# XDS100_V2.net
KiCad netlist of a schematic drawn in Altium Designer
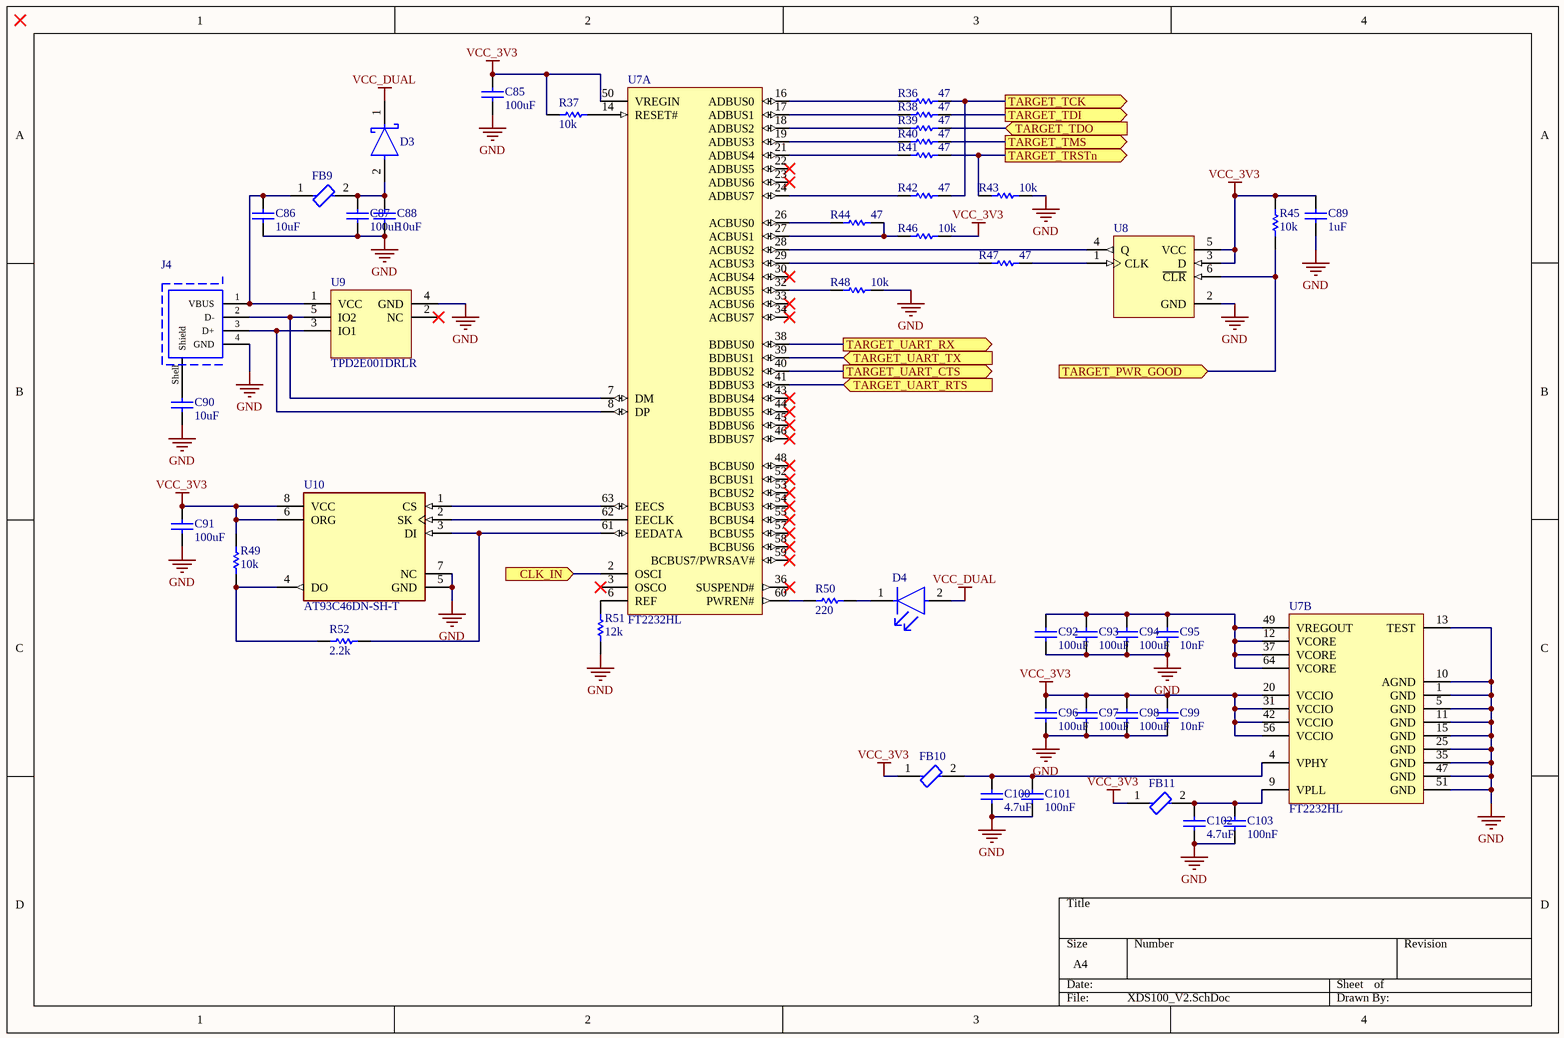
[diagram p0: XDS100_V2.SchDoc]

(export (version "E")
  (design (tool "Eeschema 10.0.6"))
  (components
    (comp (ref "C85")
      (value "100uF")
      (footprint "0805_C_S")
      (description "Capacitor")
      (fields (field (name "PUBLISHER") "Altium Limited"))
      (libsource (lib "Miscellaneous Devices") (part "Cap"))
    )
    (comp (ref "C86")
      (value "10uF")
      (footprint "0805_C_S")
      (description "Capacitor")
      (fields (field (name "PUBLISHER") "Altium Limited"))
      (libsource (lib "Miscellaneous Devices") (part "Cap"))
    )
    (comp (ref "C87")
      (value "100uF")
      (footprint "0805_C_S")
      (description "Capacitor")
      (fields (field (name "PUBLISHER") "Altium Limited"))
      (libsource (lib "Miscellaneous Devices") (part "Cap"))
    )
    (comp (ref "C88")
      (value "10uF")
      (footprint "0805_C_S")
      (description "Capacitor")
      (fields (field (name "PUBLISHER") "Altium Limited"))
      (libsource (lib "Miscellaneous Devices") (part "Cap"))
    )
    (comp (ref "C89")
      (value "1uF")
      (footprint "0805_C_S")
      (description "Capacitor")
      (fields (field (name "PUBLISHER") "Altium Limited"))
      (libsource (lib "Miscellaneous Devices") (part "Cap"))
    )
    (comp (ref "C90")
      (value "10uF")
      (footprint "0805_C_S")
      (description "Capacitor")
      (fields (field (name "PUBLISHER") "Altium Limited"))
      (libsource (lib "Miscellaneous Devices") (part "Cap"))
    )
    (comp (ref "C91")
      (value "100uF")
      (footprint "0805_C_S")
      (description "Capacitor")
      (fields (field (name "PUBLISHER") "Altium Limited"))
      (libsource (lib "Miscellaneous Devices") (part "Cap"))
    )
    (comp (ref "C92")
      (value "100uF")
      (footprint "0805_C_S")
      (description "Capacitor")
      (fields (field (name "PUBLISHER") "Altium Limited"))
      (libsource (lib "Miscellaneous Devices") (part "Cap"))
    )
    (comp (ref "C93")
      (value "100uF")
      (footprint "0805_C_S")
      (description "Capacitor")
      (fields (field (name "PUBLISHER") "Altium Limited"))
      (libsource (lib "Miscellaneous Devices") (part "Cap"))
    )
    (comp (ref "C94")
      (value "100uF")
      (footprint "0805_C_S")
      (description "Capacitor")
      (fields (field (name "PUBLISHER") "Altium Limited"))
      (libsource (lib "Miscellaneous Devices") (part "Cap"))
    )
    (comp (ref "C95")
      (value "10nF")
      (footprint "0805_C_S")
      (description "Capacitor")
      (fields (field (name "PUBLISHER") "Altium Limited"))
      (libsource (lib "Miscellaneous Devices") (part "Cap"))
    )
    (comp (ref "C96")
      (value "100uF")
      (footprint "0805_C_S")
      (description "Capacitor")
      (fields (field (name "PUBLISHER") "Altium Limited"))
      (libsource (lib "Miscellaneous Devices") (part "Cap"))
    )
    (comp (ref "C97")
      (value "100uF")
      (footprint "0805_C_S")
      (description "Capacitor")
      (fields (field (name "PUBLISHER") "Altium Limited"))
      (libsource (lib "Miscellaneous Devices") (part "Cap"))
    )
    (comp (ref "C98")
      (value "100uF")
      (footprint "0805_C_S")
      (description "Capacitor")
      (fields (field (name "PUBLISHER") "Altium Limited"))
      (libsource (lib "Miscellaneous Devices") (part "Cap"))
    )
    (comp (ref "C99")
      (value "10nF")
      (footprint "0805_C_S")
      (description "Capacitor")
      (fields (field (name "PUBLISHER") "Altium Limited"))
      (libsource (lib "Miscellaneous Devices") (part "Cap"))
    )
    (comp (ref "C100")
      (value "4.7uF")
      (footprint "0805_C_S")
      (description "Capacitor")
      (fields (field (name "PUBLISHER") "Altium Limited"))
      (libsource (lib "Miscellaneous Devices") (part "Cap"))
    )
    (comp (ref "C101")
      (value "100nF")
      (footprint "0805_C_S")
      (description "Capacitor")
      (fields (field (name "PUBLISHER") "Altium Limited"))
      (libsource (lib "Miscellaneous Devices") (part "Cap"))
    )
    (comp (ref "C102")
      (value "4.7uF")
      (footprint "0805_C_S")
      (description "Capacitor")
      (fields (field (name "PUBLISHER") "Altium Limited"))
      (libsource (lib "Miscellaneous Devices") (part "Cap"))
    )
    (comp (ref "C103")
      (value "100nF")
      (footprint "0805_C_S")
      (description "Capacitor")
      (fields (field (name "PUBLISHER") "Altium Limited"))
      (libsource (lib "Miscellaneous Devices") (part "Cap"))
    )
    (comp (ref "D3")
      (value "MBR0520LT1G")
      (footprint "FP-425-04-IPC_C")
      (description "DIODE SCHOTTKY 20V 500MA SOD123")
      (libsource (lib "Altium Content Vault") (part "1d6ec82d83fb6aee721767c19dac4b9"))
    )
    (comp (ref "D4")
      (value "LTST-C150AKT")
      (footprint "FP-LTST-C150AKT-MFG")
      (description "LED AMBER CLEAR SMD")
      (fields
        (field (name "MANUFACTURER") "Lite-On")
        (field (name "OCTOPART") "https://octopart.com/ltst-c150akt-lite-on-549804")
      )
      (libsource (lib "Altium Content Vault") (part "8706943c75ba83719d021d2fdc84c58"))
    )
    (comp (ref "FB9")
      (value "BLM21PG221SN1D")
      (footprint "FP-BLM21-0_2-t0_85-e0_5-IPC_B")
      (description "Chip Ferrite Bead, 0805, 220Ω @ 100MHz, 0.045Ω, 25%, 2A")
      (fields (field (name "TOLERANCE") "25%"))
      (libsource (lib "Altium Content Vault") (part "5f30dd21d616792df468990f7003faa"))
    )
    (comp (ref "FB10")
      (value "BLM21PG221SN1D")
      (footprint "FP-BLM21-0_2-t0_85-e0_5-IPC_B")
      (description "Chip Ferrite Bead, 0805, 220Ω @ 100MHz, 0.045Ω, 25%, 2A")
      (fields (field (name "TOLERANCE") "25%"))
      (libsource (lib "Altium Content Vault") (part "5f30dd21d616792df468990f7003faa"))
    )
    (comp (ref "FB11")
      (value "BLM21PG221SN1D")
      (footprint "FP-BLM21-0_2-t0_85-e0_5-IPC_B")
      (description "Chip Ferrite Bead, 0805, 220Ω @ 100MHz, 0.045Ω, 25%, 2A")
      (fields (field (name "TOLERANCE") "25%"))
      (libsource (lib "Altium Content Vault") (part "5f30dd21d616792df468990f7003faa"))
    )
    (comp (ref "J4")
      (value "62900416021")
      (footprint "62900416021")
      (description "USB 2.0 Type A Receptacle WR-COM, Horizontal, SMT")
      (fields (field (name "MANUFACTURER") "Wurth Elektronik") (field (name "PUBLISHER") "WurthElektronik"))
      (libsource (lib "Altium Content Vault") (part "WE-USB-4-1SHLD"))
    )
    (comp (ref "R36")
      (value "47")
      (footprint "0805_R_S")
      (description "Resistor")
      (fields (field (name "PUBLISHER") "Altium Limited"))
      (libsource (lib "Miscellaneous Devices") (part "Res1"))
    )
    (comp (ref "R37")
      (value "10k")
      (footprint "0805_R_S")
      (description "Resistor")
      (fields (field (name "PUBLISHER") "Altium Limited"))
      (libsource (lib "Miscellaneous Devices") (part "Res1"))
    )
    (comp (ref "R38")
      (value "47")
      (footprint "0805_R_S")
      (description "Resistor")
      (fields (field (name "PUBLISHER") "Altium Limited"))
      (libsource (lib "Miscellaneous Devices") (part "Res1"))
    )
    (comp (ref "R39")
      (value "47")
      (footprint "0805_R_S")
      (description "Resistor")
      (fields (field (name "PUBLISHER") "Altium Limited"))
      (libsource (lib "Miscellaneous Devices") (part "Res1"))
    )
    (comp (ref "R40")
      (value "47")
      (footprint "0805_R_S")
      (description "Resistor")
      (fields (field (name "PUBLISHER") "Altium Limited"))
      (libsource (lib "Miscellaneous Devices") (part "Res1"))
    )
    (comp (ref "R41")
      (value "47")
      (footprint "0805_R_S")
      (description "Resistor")
      (fields (field (name "PUBLISHER") "Altium Limited"))
      (libsource (lib "Miscellaneous Devices") (part "Res1"))
    )
    (comp (ref "R42")
      (value "47")
      (footprint "0805_R_S")
      (description "Resistor")
      (fields (field (name "PUBLISHER") "Altium Limited"))
      (libsource (lib "Miscellaneous Devices") (part "Res1"))
    )
    (comp (ref "R43")
      (value "10k")
      (footprint "0805_R_S")
      (description "Resistor")
      (fields (field (name "PUBLISHER") "Altium Limited"))
      (libsource (lib "Miscellaneous Devices") (part "Res1"))
    )
    (comp (ref "R44")
      (value "47")
      (footprint "0805_R_S")
      (description "Resistor")
      (fields (field (name "PUBLISHER") "Altium Limited"))
      (libsource (lib "Miscellaneous Devices") (part "Res1"))
    )
    (comp (ref "R45")
      (value "10k")
      (footprint "0805_R_S")
      (description "Resistor")
      (fields (field (name "PUBLISHER") "Altium Limited"))
      (libsource (lib "Miscellaneous Devices") (part "Res1"))
    )
    (comp (ref "R46")
      (value "10k")
      (footprint "0805_R_S")
      (description "Resistor")
      (fields (field (name "PUBLISHER") "Altium Limited"))
      (libsource (lib "Miscellaneous Devices") (part "Res1"))
    )
    (comp (ref "R47")
      (value "47")
      (footprint "0805_R_S")
      (description "Resistor")
      (fields (field (name "PUBLISHER") "Altium Limited"))
      (libsource (lib "Miscellaneous Devices") (part "Res1"))
    )
    (comp (ref "R48")
      (value "10k")
      (footprint "0805_R_S")
      (description "Resistor")
      (fields (field (name "PUBLISHER") "Altium Limited"))
      (libsource (lib "Miscellaneous Devices") (part "Res1"))
    )
    (comp (ref "R49")
      (value "10k")
      (footprint "0805_R_S")
      (description "Resistor")
      (fields (field (name "PUBLISHER") "Altium Limited"))
      (libsource (lib "Miscellaneous Devices") (part "Res1"))
    )
    (comp (ref "R50")
      (value "220")
      (footprint "0805_R_S")
      (description "Resistor")
      (fields (field (name "PUBLISHER") "Altium Limited"))
      (libsource (lib "Miscellaneous Devices") (part "Res1"))
    )
    (comp (ref "R51")
      (value "12k")
      (footprint "0805_R_S")
      (description "Resistor")
      (fields (field (name "PUBLISHER") "Altium Limited"))
      (libsource (lib "Miscellaneous Devices") (part "Res1"))
    )
    (comp (ref "R52")
      (value "2.2k")
      (footprint "0805_R_S")
      (description "Resistor")
      (fields (field (name "PUBLISHER") "Altium Limited"))
      (libsource (lib "Miscellaneous Devices") (part "Res1"))
    )
    (comp (ref "U7")
      (value "FT2232HL")
      (footprint "FTDI-LQFP-64_L")
      (fields (field (name "MANUFACTURER") "FTDI"))
      (libsource (lib "") (part "FTDI-FT2232HL-LQFP-64_1"))
    )
    (comp (ref "U8")
      (value "SN74LVC1G175DBVR")
      (footprint "DBV0006A_L")
      (description "Single D-Type Flip-Flop with Asynchronous Clear, DBV0006A, LARGE T&R")
      (fields
        (field (name "MANUFACTURER") "Texas Instruments")
        (field (name "GENERIC PART NUMBER") "SN74LVC1G175")
      )
      (libsource (lib "Altium Content Vault") (part "TI-SN74LVC1G175-6"))
    )
    (comp (ref "U9")
      (value "TPD2E001DRLR")
      (footprint "DRL0005A_L")
      (fields (field (name "MANUFACTURER") "Texas Instruments"))
      (libsource (lib "Altium Content Vault") (part "TI-TPD2E001-SOT_DRL-5"))
    )
    (comp (ref "U10")
      (value "AT93C46DN-SH-T")
      (footprint "FP-C04-057-SN-MFG")
      (description "IC EEPROM 1K SPI 2MHZ 8SOIC")
      (fields
        (field (name "MANUFACTURER") "Microchip")
        (field (name "OCTOPART") "https://octopart.com/at93c46dn-sh-t-microchip-77759177")
      )
      (libsource (lib "Altium Content Vault") (part "8bb9afc094b350e480db350c7247e52"))
    )
  )
  (nets
    (net (code "1") (name "/CLK_IN") (class "Default")
      (node (ref "U7") (pin "2") (pinfunction "OSCI_2") (pintype "passive"))
    )
    (net (code "2") (name "/TARGET_PWR_GOOD") (class "Default")
      (node (ref "R45") (pin "2") (pinfunction "2_2") (pintype "passive"))
      (node (ref "U8") (pin "6") (pinfunction "~{CLR}_6") (pintype "input"))
    )
    (net (code "3") (name "/TARGET_TCK") (class "Default")
      (node (ref "R36") (pin "2") (pinfunction "2_2") (pintype "passive"))
      (node (ref "R42") (pin "2") (pinfunction "2_2") (pintype "passive"))
    )
    (net (code "4") (name "/TARGET_TDI") (class "Default")
      (node (ref "R38") (pin "2") (pinfunction "2_2") (pintype "passive"))
    )
    (net (code "5") (name "/TARGET_TDO") (class "Default")
      (node (ref "R39") (pin "2") (pinfunction "2_2") (pintype "passive"))
    )
    (net (code "6") (name "/TARGET_TMS") (class "Default")
      (node (ref "R40") (pin "2") (pinfunction "2_2") (pintype "passive"))
    )
    (net (code "7") (name "/TARGET_TRSTn") (class "Default")
      (node (ref "R41") (pin "2") (pinfunction "2_2") (pintype "passive"))
      (node (ref "R43") (pin "1") (pinfunction "1_1") (pintype "passive"))
    )
    (net (code "8") (name "/TARGET_UART_CTS") (class "Default")
      (node (ref "U7") (pin "40") (pinfunction "BDBUS2_40") (pintype "bidirectional"))
    )
    (net (code "9") (name "/TARGET_UART_RTS") (class "Default")
      (node (ref "U7") (pin "41") (pinfunction "BDBUS3_41") (pintype "bidirectional"))
    )
    (net (code "10") (name "/TARGET_UART_RX") (class "Default")
      (node (ref "U7") (pin "38") (pinfunction "BDBUS0_38") (pintype "bidirectional"))
    )
    (net (code "11") (name "/TARGET_UART_TX") (class "Default")
      (node (ref "U7") (pin "39") (pinfunction "BDBUS1_39") (pintype "bidirectional"))
    )
    (net (code "12") (name "GND") (class "Default")
      (node (ref "C100") (pin "1") (pinfunction "1_1") (pintype "passive"))
      (node (ref "C101") (pin "1") (pinfunction "1_1") (pintype "passive"))
      (node (ref "C102") (pin "1") (pinfunction "1_1") (pintype "passive"))
      (node (ref "C103") (pin "1") (pinfunction "1_1") (pintype "passive"))
      (node (ref "C85") (pin "1") (pinfunction "1_1") (pintype "passive"))
      (node (ref "C86") (pin "1") (pinfunction "1_1") (pintype "passive"))
      (node (ref "C87") (pin "1") (pinfunction "1_1") (pintype "passive"))
      (node (ref "C88") (pin "1") (pinfunction "1_1") (pintype "passive"))
      (node (ref "C89") (pin "1") (pinfunction "1_1") (pintype "passive"))
      (node (ref "C90") (pin "1") (pinfunction "1_1") (pintype "passive"))
      (node (ref "C91") (pin "1") (pinfunction "1_1") (pintype "passive"))
      (node (ref "C92") (pin "1") (pinfunction "1_1") (pintype "passive"))
      (node (ref "C93") (pin "1") (pinfunction "1_1") (pintype "passive"))
      (node (ref "C94") (pin "1") (pinfunction "1_1") (pintype "passive"))
      (node (ref "C95") (pin "1") (pinfunction "1_1") (pintype "passive"))
      (node (ref "C96") (pin "1") (pinfunction "1_1") (pintype "passive"))
      (node (ref "C97") (pin "1") (pinfunction "1_1") (pintype "passive"))
      (node (ref "C98") (pin "1") (pinfunction "1_1") (pintype "passive"))
      (node (ref "C99") (pin "1") (pinfunction "1_1") (pintype "passive"))
      (node (ref "J4") (pin "4") (pinfunction "GND_4") (pintype "passive"))
      (node (ref "R43") (pin "2") (pinfunction "2_2") (pintype "passive"))
      (node (ref "R48") (pin "2") (pinfunction "2_2") (pintype "passive"))
      (node (ref "R51") (pin "2") (pinfunction "2_2") (pintype "passive"))
      (node (ref "U10") (pin "5") (pinfunction "GND_5") (pintype "power_in"))
      (node (ref "U10") (pin "7") (pinfunction "NC_7") (pintype "passive"))
      (node (ref "U7") (pin "1") (pinfunction "GND_1") (pintype "power_in"))
      (node (ref "U7") (pin "10") (pinfunction "AGND_10") (pintype "power_in"))
      (node (ref "U7") (pin "11") (pinfunction "GND_11") (pintype "power_in"))
      (node (ref "U7") (pin "13") (pinfunction "TEST_13") (pintype "passive"))
      (node (ref "U7") (pin "15") (pinfunction "GND_15") (pintype "power_in"))
      (node (ref "U7") (pin "25") (pinfunction "GND_25") (pintype "power_in"))
      (node (ref "U7") (pin "35") (pinfunction "GND_35") (pintype "power_in"))
      (node (ref "U7") (pin "47") (pinfunction "GND_47") (pintype "power_in"))
      (node (ref "U7") (pin "5") (pinfunction "GND_5") (pintype "power_in"))
      (node (ref "U7") (pin "51") (pinfunction "GND_51") (pintype "power_in"))
      (node (ref "U8") (pin "2") (pinfunction "GND_2") (pintype "power_in"))
      (node (ref "U9") (pin "4") (pinfunction "GND_4") (pintype "power_in"))
    )
    (net (code "13") (name "Net-(D3-A)") (class "Default")
      (node (ref "C87") (pin "2") (pinfunction "2_2") (pintype "passive"))
      (node (ref "C88") (pin "2") (pinfunction "2_2") (pintype "passive"))
      (node (ref "D3") (pin "2") (pinfunction "A_2") (pintype "passive"))
      (node (ref "FB9") (pin "2") (pinfunction "2_2") (pintype "passive"))
    )
    (net (code "14") (name "Net-(D4-C)") (class "Default")
      (node (ref "D4") (pin "1") (pinfunction "C_1") (pintype "passive"))
      (node (ref "R50") (pin "2") (pinfunction "2_2") (pintype "passive"))
    )
    (net (code "15") (name "Net-(J4-D+)") (class "Default")
      (node (ref "J4") (pin "3") (pinfunction "D+_3") (pintype "passive"))
      (node (ref "U7") (pin "8") (pinfunction "DP_8") (pintype "bidirectional"))
      (node (ref "U9") (pin "3") (pinfunction "IO1_3") (pintype "passive"))
    )
    (net (code "16") (name "Net-(J4-D-)") (class "Default")
      (node (ref "J4") (pin "2") (pinfunction "D-_2") (pintype "passive"))
      (node (ref "U7") (pin "7") (pinfunction "DM_7") (pintype "bidirectional"))
      (node (ref "U9") (pin "5") (pinfunction "IO2_5") (pintype "passive"))
    )
    (net (code "17") (name "Net-(J4-Shield)") (class "Default")
      (node (ref "C90") (pin "2") (pinfunction "2_2") (pintype "passive"))
      (node (ref "J4") (pin "Shell") (pinfunction "Shield_Shell") (pintype "passive"))
    )
    (net (code "18") (name "Net-(J4-VBUS)") (class "Default")
      (node (ref "C86") (pin "2") (pinfunction "2_2") (pintype "passive"))
      (node (ref "FB9") (pin "1") (pinfunction "1_1") (pintype "passive"))
      (node (ref "J4") (pin "1") (pinfunction "VBUS_1") (pintype "passive"))
      (node (ref "U9") (pin "1") (pinfunction "VCC_1") (pintype "power_in"))
    )
    (net (code "19") (name "Net-(U7A-ACBUS0)") (class "Default")
      (node (ref "R44") (pin "1") (pinfunction "1_1") (pintype "passive"))
      (node (ref "U7") (pin "26") (pinfunction "ACBUS0_26") (pintype "bidirectional"))
    )
    (net (code "20") (name "Net-(U7A-ACBUS1)") (class "Default")
      (node (ref "R44") (pin "2") (pinfunction "2_2") (pintype "passive"))
      (node (ref "R46") (pin "1") (pinfunction "1_1") (pintype "passive"))
      (node (ref "U7") (pin "27") (pinfunction "ACBUS1_27") (pintype "bidirectional"))
    )
    (net (code "21") (name "Net-(U7A-ACBUS2)") (class "Default")
      (node (ref "U7") (pin "28") (pinfunction "ACBUS2_28") (pintype "bidirectional"))
      (node (ref "U8") (pin "4") (pinfunction "Q_4") (pintype "output"))
    )
    (net (code "22") (name "Net-(U7A-ACBUS3)") (class "Default")
      (node (ref "R47") (pin "1") (pinfunction "1_1") (pintype "passive"))
      (node (ref "U7") (pin "29") (pinfunction "ACBUS3_29") (pintype "bidirectional"))
    )
    (net (code "23") (name "Net-(U7A-ACBUS5)") (class "Default")
      (node (ref "R48") (pin "1") (pinfunction "1_1") (pintype "passive"))
      (node (ref "U7") (pin "32") (pinfunction "ACBUS5_32") (pintype "bidirectional"))
    )
    (net (code "24") (name "Net-(U7A-ADBUS0)") (class "Default")
      (node (ref "R36") (pin "1") (pinfunction "1_1") (pintype "passive"))
      (node (ref "U7") (pin "16") (pinfunction "ADBUS0_16") (pintype "bidirectional"))
    )
    (net (code "25") (name "Net-(U7A-ADBUS1)") (class "Default")
      (node (ref "R38") (pin "1") (pinfunction "1_1") (pintype "passive"))
      (node (ref "U7") (pin "17") (pinfunction "ADBUS1_17") (pintype "bidirectional"))
    )
    (net (code "26") (name "Net-(U7A-ADBUS2)") (class "Default")
      (node (ref "R39") (pin "1") (pinfunction "1_1") (pintype "passive"))
      (node (ref "U7") (pin "18") (pinfunction "ADBUS2_18") (pintype "bidirectional"))
    )
    (net (code "27") (name "Net-(U7A-ADBUS3)") (class "Default")
      (node (ref "R40") (pin "1") (pinfunction "1_1") (pintype "passive"))
      (node (ref "U7") (pin "19") (pinfunction "ADBUS3_19") (pintype "bidirectional"))
    )
    (net (code "28") (name "Net-(U7A-ADBUS4)") (class "Default")
      (node (ref "R41") (pin "1") (pinfunction "1_1") (pintype "passive"))
      (node (ref "U7") (pin "21") (pinfunction "ADBUS4_21") (pintype "bidirectional"))
    )
    (net (code "29") (name "Net-(U7A-ADBUS7)") (class "Default")
      (node (ref "R42") (pin "1") (pinfunction "1_1") (pintype "passive"))
      (node (ref "U7") (pin "24") (pinfunction "ADBUS7_24") (pintype "bidirectional"))
    )
    (net (code "30") (name "Net-(U7A-PWREN#)") (class "Default")
      (node (ref "R50") (pin "1") (pinfunction "1_1") (pintype "passive"))
      (node (ref "U7") (pin "60") (pinfunction "PWREN#_60") (pintype "output"))
    )
    (net (code "31") (name "Net-(U7A-REF)") (class "Default")
      (node (ref "R51") (pin "1") (pinfunction "1_1") (pintype "passive"))
      (node (ref "U7") (pin "6") (pinfunction "REF_6") (pintype "passive"))
    )
    (net (code "32") (name "Net-(U7A-RESET#)") (class "Default")
      (node (ref "R37") (pin "2") (pinfunction "2_2") (pintype "passive"))
      (node (ref "U7") (pin "14") (pinfunction "RESET#_14") (pintype "input"))
    )
    (net (code "33") (name "Net-(U7B-VPHY)") (class "Default")
      (node (ref "C100") (pin "2") (pinfunction "2_2") (pintype "passive"))
      (node (ref "C101") (pin "2") (pinfunction "2_2") (pintype "passive"))
      (node (ref "FB10") (pin "2") (pinfunction "2_2") (pintype "passive"))
      (node (ref "U7") (pin "4") (pinfunction "VPHY_4") (pintype "power_in"))
    )
    (net (code "34") (name "Net-(U7B-VPLL)") (class "Default")
      (node (ref "C102") (pin "2") (pinfunction "2_2") (pintype "passive"))
      (node (ref "C103") (pin "2") (pinfunction "2_2") (pintype "passive"))
      (node (ref "FB11") (pin "2") (pinfunction "2_2") (pintype "passive"))
      (node (ref "U7") (pin "9") (pinfunction "VPLL_9") (pintype "power_in"))
    )
    (net (code "35") (name "Net-(U7B-VREGOUT)") (class "Default")
      (node (ref "C92") (pin "2") (pinfunction "2_2") (pintype "passive"))
      (node (ref "C93") (pin "2") (pinfunction "2_2") (pintype "passive"))
      (node (ref "C94") (pin "2") (pinfunction "2_2") (pintype "passive"))
      (node (ref "C95") (pin "2") (pinfunction "2_2") (pintype "passive"))
      (node (ref "U7") (pin "12") (pinfunction "VCORE_12") (pintype "power_in"))
      (node (ref "U7") (pin "37") (pinfunction "VCORE_37") (pintype "power_in"))
      (node (ref "U7") (pin "49") (pinfunction "VREGOUT_49") (pintype "power_in"))
      (node (ref "U7") (pin "64") (pinfunction "VCORE_64") (pintype "power_in"))
    )
    (net (code "36") (name "Net-(U8-CLK)") (class "Default")
      (node (ref "R47") (pin "2") (pinfunction "2_2") (pintype "passive"))
      (node (ref "U8") (pin "1") (pinfunction "CLK_1") (pintype "input"))
    )
    (net (code "37") (name "Net-(U10-CS)") (class "Default")
      (node (ref "U10") (pin "1") (pinfunction "CS_1") (pintype "input"))
      (node (ref "U7") (pin "63") (pinfunction "EECS_63") (pintype "bidirectional"))
    )
    (net (code "38") (name "Net-(U10-DI)") (class "Default")
      (node (ref "R52") (pin "2") (pinfunction "2_2") (pintype "passive"))
      (node (ref "U10") (pin "3") (pinfunction "DI_3") (pintype "input"))
      (node (ref "U7") (pin "61") (pinfunction "EEDATA_61") (pintype "bidirectional"))
    )
    (net (code "39") (name "Net-(U10-DO)") (class "Default")
      (node (ref "R49") (pin "2") (pinfunction "2_2") (pintype "passive"))
      (node (ref "R52") (pin "1") (pinfunction "1_1") (pintype "passive"))
      (node (ref "U10") (pin "4") (pinfunction "DO_4") (pintype "output"))
    )
    (net (code "40") (name "Net-(U10-SK)") (class "Default")
      (node (ref "U10") (pin "2") (pinfunction "SK_2") (pintype "input"))
      (node (ref "U7") (pin "62") (pinfunction "EECLK_62") (pintype "tri_state"))
    )
    (net (code "41") (name "VCC_3V3") (class "Default")
      (node (ref "C85") (pin "2") (pinfunction "2_2") (pintype "passive"))
      (node (ref "C89") (pin "2") (pinfunction "2_2") (pintype "passive"))
      (node (ref "C91") (pin "2") (pinfunction "2_2") (pintype "passive"))
      (node (ref "C96") (pin "2") (pinfunction "2_2") (pintype "passive"))
      (node (ref "C97") (pin "2") (pinfunction "2_2") (pintype "passive"))
      (node (ref "C98") (pin "2") (pinfunction "2_2") (pintype "passive"))
      (node (ref "C99") (pin "2") (pinfunction "2_2") (pintype "passive"))
      (node (ref "FB10") (pin "1") (pinfunction "1_1") (pintype "passive"))
      (node (ref "FB11") (pin "1") (pinfunction "1_1") (pintype "passive"))
      (node (ref "R37") (pin "1") (pinfunction "1_1") (pintype "passive"))
      (node (ref "R45") (pin "1") (pinfunction "1_1") (pintype "passive"))
      (node (ref "R46") (pin "2") (pinfunction "2_2") (pintype "passive"))
      (node (ref "R49") (pin "1") (pinfunction "1_1") (pintype "passive"))
      (node (ref "U10") (pin "6") (pinfunction "ORG_6") (pintype "passive"))
      (node (ref "U10") (pin "8") (pinfunction "VCC_8") (pintype "power_in"))
      (node (ref "U7") (pin "20") (pinfunction "VCCIO_20") (pintype "power_in"))
      (node (ref "U7") (pin "31") (pinfunction "VCCIO_31") (pintype "power_in"))
      (node (ref "U7") (pin "42") (pinfunction "VCCIO_42") (pintype "power_in"))
      (node (ref "U7") (pin "50") (pinfunction "VREGIN_50") (pintype "power_in"))
      (node (ref "U7") (pin "56") (pinfunction "VCCIO_56") (pintype "power_in"))
      (node (ref "U8") (pin "3") (pinfunction "D_3") (pintype "input"))
      (node (ref "U8") (pin "5") (pinfunction "VCC_5") (pintype "power_in"))
    )
    (net (code "42") (name "VCC_DUAL") (class "Default")
      (node (ref "D3") (pin "1") (pinfunction "C_1") (pintype "passive"))
      (node (ref "D4") (pin "2") (pinfunction "A_2") (pintype "passive"))
    )
    (net (code "43") (name "unconnected-(U7A-ACBUS4-Pad30)") (class "Default")
      (node (ref "U7") (pin "30") (pinfunction "ACBUS4_30") (pintype "bidirectional+no_connect"))
    )
    (net (code "44") (name "unconnected-(U7A-ACBUS6-Pad33)") (class "Default")
      (node (ref "U7") (pin "33") (pinfunction "ACBUS6_33") (pintype "bidirectional+no_connect"))
    )
    (net (code "45") (name "unconnected-(U7A-ACBUS7-Pad34)") (class "Default")
      (node (ref "U7") (pin "34") (pinfunction "ACBUS7_34") (pintype "bidirectional+no_connect"))
    )
    (net (code "46") (name "unconnected-(U7A-ADBUS5-Pad22)") (class "Default")
      (node (ref "U7") (pin "22") (pinfunction "ADBUS5_22") (pintype "bidirectional+no_connect"))
    )
    (net (code "47") (name "unconnected-(U7A-ADBUS6-Pad23)") (class "Default")
      (node (ref "U7") (pin "23") (pinfunction "ADBUS6_23") (pintype "bidirectional+no_connect"))
    )
    (net (code "48") (name "unconnected-(U7A-BCBUS0-Pad48)") (class "Default")
      (node (ref "U7") (pin "48") (pinfunction "BCBUS0_48") (pintype "bidirectional+no_connect"))
    )
    (net (code "49") (name "unconnected-(U7A-BCBUS1-Pad52)") (class "Default")
      (node (ref "U7") (pin "52") (pinfunction "BCBUS1_52") (pintype "bidirectional+no_connect"))
    )
    (net (code "50") (name "unconnected-(U7A-BCBUS2-Pad53)") (class "Default")
      (node (ref "U7") (pin "53") (pinfunction "BCBUS2_53") (pintype "bidirectional+no_connect"))
    )
    (net (code "51") (name "unconnected-(U7A-BCBUS3-Pad54)") (class "Default")
      (node (ref "U7") (pin "54") (pinfunction "BCBUS3_54") (pintype "bidirectional+no_connect"))
    )
    (net (code "52") (name "unconnected-(U7A-BCBUS4-Pad55)") (class "Default")
      (node (ref "U7") (pin "55") (pinfunction "BCBUS4_55") (pintype "bidirectional+no_connect"))
    )
    (net (code "53") (name "unconnected-(U7A-BCBUS5-Pad57)") (class "Default")
      (node (ref "U7") (pin "57") (pinfunction "BCBUS5_57") (pintype "bidirectional+no_connect"))
    )
    (net (code "54") (name "unconnected-(U7A-BCBUS6-Pad58)") (class "Default")
      (node (ref "U7") (pin "58") (pinfunction "BCBUS6_58") (pintype "bidirectional+no_connect"))
    )
    (net (code "55") (name "unconnected-(U7A-BCBUS7{slash}PWRSAV#-Pad59)") (class "Default")
      (node (ref "U7") (pin "59") (pinfunction "BCBUS7/PWRSAV#_59") (pintype "bidirectional+no_connect"))
    )
    (net (code "56") (name "unconnected-(U7A-BDBUS4-Pad43)") (class "Default")
      (node (ref "U7") (pin "43") (pinfunction "BDBUS4_43") (pintype "bidirectional+no_connect"))
    )
    (net (code "57") (name "unconnected-(U7A-BDBUS5-Pad44)") (class "Default")
      (node (ref "U7") (pin "44") (pinfunction "BDBUS5_44") (pintype "bidirectional+no_connect"))
    )
    (net (code "58") (name "unconnected-(U7A-BDBUS6-Pad45)") (class "Default")
      (node (ref "U7") (pin "45") (pinfunction "BDBUS6_45") (pintype "bidirectional+no_connect"))
    )
    (net (code "59") (name "unconnected-(U7A-BDBUS7-Pad46)") (class "Default")
      (node (ref "U7") (pin "46") (pinfunction "BDBUS7_46") (pintype "bidirectional+no_connect"))
    )
    (net (code "60") (name "unconnected-(U7A-OSCO-Pad3)") (class "Default")
      (node (ref "U7") (pin "3") (pinfunction "OSCO_3") (pintype "passive+no_connect"))
    )
    (net (code "61") (name "unconnected-(U7A-SUSPEND#-Pad36)") (class "Default")
      (node (ref "U7") (pin "36") (pinfunction "SUSPEND#_36") (pintype "output+no_connect"))
    )
    (net (code "62") (name "unconnected-(U9-NC-Pad2)") (class "Default")
      (node (ref "U9") (pin "2") (pinfunction "NC_2") (pintype "passive+no_connect"))
    )
  )
)
